# Sheet_ascii.net
KiCad netlist of a schematic drawn in Altium Designer
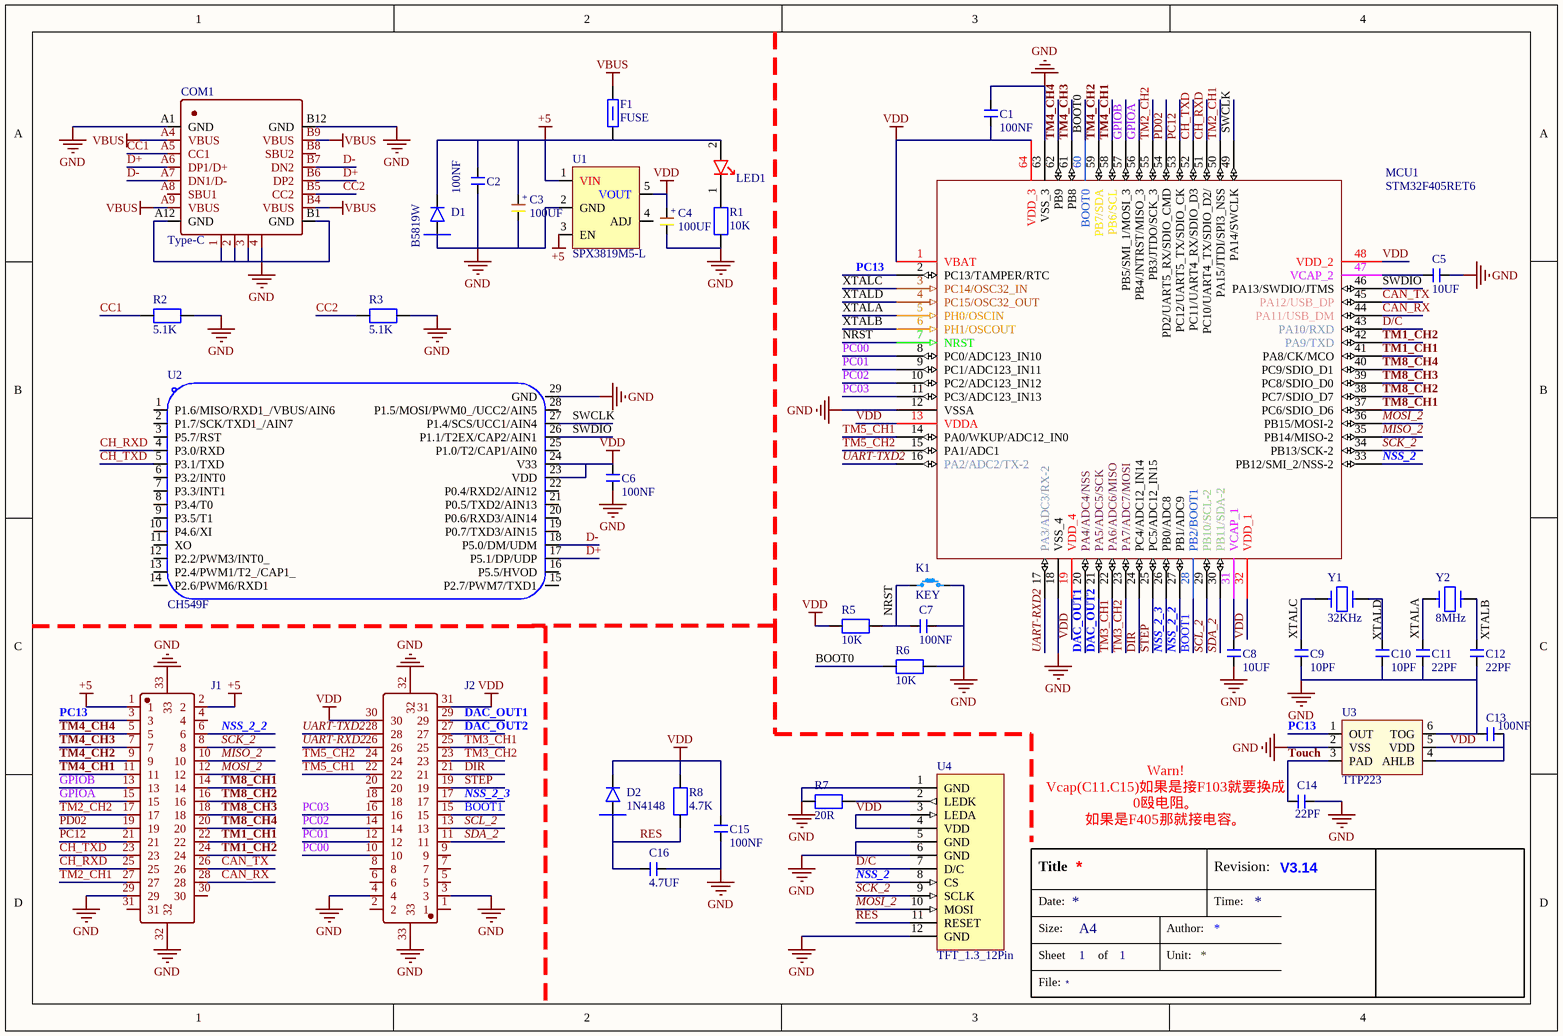
[diagram p0: Sheet_ascii.schDoc]

(export (version "E")
  (design (tool "Eeschema 10.0.6"))
  (components
    (comp (ref "C1")
      (value "100NF")
      (footprint "CAP_0603")
      (description "CAP  12~50V")
      (libsource (lib "User") (part "CAP"))
    )
    (comp (ref "C2")
      (value "100NF")
      (footprint "CAP_0603")
      (description "CAP  12~50V")
      (libsource (lib "User") (part "CAP"))
    )
    (comp (ref "C3")
      (value "100UF")
      (footprint "CAP_3216_A")
      (description "CAP  6~12V  钽电容")
      (libsource (lib "User") (part "CAP_TA"))
    )
    (comp (ref "C4")
      (value "100UF")
      (footprint "CAP_3216_A")
      (description "CAP  6~12V  钽电容")
      (libsource (lib "User") (part "CAP_TA"))
    )
    (comp (ref "C5")
      (value "10UF")
      (footprint "CAP_0603")
      (description "CAP  12~50V")
      (libsource (lib "User") (part "CAP"))
    )
    (comp (ref "C6")
      (value "100NF")
      (footprint "CAP_0603")
      (description "CAP  12~50V")
      (libsource (lib "User") (part "CAP"))
    )
    (comp (ref "C7")
      (value "100NF")
      (footprint "CAP_0603")
      (description "CAP  12~50V")
      (libsource (lib "User") (part "CAP"))
    )
    (comp (ref "C8")
      (value "10UF")
      (footprint "CAP_0603")
      (description "CAP  12~50V")
      (libsource (lib "User") (part "CAP"))
    )
    (comp (ref "C9")
      (value "10PF")
      (footprint "CAP_0603")
      (description "CAP  12~50V")
      (libsource (lib "User") (part "CAP"))
    )
    (comp (ref "C10")
      (value "10PF")
      (footprint "CAP_0603")
      (description "CAP  12~50V")
      (libsource (lib "User") (part "CAP"))
    )
    (comp (ref "C11")
      (value "22PF")
      (footprint "CAP_0603")
      (description "CAP  12~50V")
      (libsource (lib "User") (part "CAP"))
    )
    (comp (ref "C12")
      (value "22PF")
      (footprint "CAP_0603")
      (description "CAP  12~50V")
      (libsource (lib "User") (part "CAP"))
    )
    (comp (ref "C13")
      (value "100NF")
      (footprint "CAP_0603")
      (description "CAP  12~50V")
      (libsource (lib "User") (part "CAP"))
    )
    (comp (ref "C14")
      (value "22PF")
      (footprint "CAP_0603")
      (description "CAP  12~50V")
      (libsource (lib "User") (part "CAP"))
    )
    (comp (ref "C15")
      (value "100NF")
      (footprint "CAP_0603")
      (description "CAP  12~50V")
      (libsource (lib "User") (part "CAP"))
    )
    (comp (ref "C16")
      (value "4.7UF")
      (footprint "CAP_0603")
      (description "CAP  12~50V")
      (libsource (lib "User") (part "CAP"))
    )
    (comp (ref "COM1")
      (value "Type-C")
      (footprint "USB-Type-C_16A")
      (description "USB")
      (libsource (lib "User") (part "USB-type_c"))
    )
    (comp (ref "D1")
      (value "B5819W")
      (footprint "DIODE_SOD123")
      (description "Diode_肖特基/二极管")
      (libsource (lib "User") (part "Diode-SM"))
    )
    (comp (ref "D2")
      (value "1N4148")
      (footprint "DIODE_SOD123")
      (description "Diode_肖特基/二极管")
      (libsource (lib "User") (part "Diode-SM"))
    )
    (comp (ref "F1") (value "FUSE") (footprint "Fuse_0603") (libsource (lib "User") (part "FUSE")))
    (comp (ref "J1")
      (value "31PIN")
      (footprint "BTB-DM3-31P")
      (description "BTB")
      (libsource (lib "User") (part "BTB_DF3_31Pin"))
    )
    (comp (ref "J2")
      (value "31PIN")
      (footprint "BTB-DM3-31P")
      (description "BTB")
      (libsource (lib "User") (part "BTB_DF3_31Pin"))
    )
    (comp (ref "K1")
      (value "KEY")
      (footprint "KEY_SMD")
      (description "Key")
      (libsource (lib "User") (part "KEY"))
    )
    (comp (ref "LED1")
      (value "LED_R/G/B/Y")
      (footprint "LED_0603_R")
      (description "LED")
      (libsource (lib "User") (part "LED_SMT"))
    )
    (comp (ref "MCU1")
      (value "STM32F405RET6")
      (footprint "LQFP_64_10X10")
      (description "MCU")
      (libsource (lib "User") (part "STM32f4_R"))
    )
    (comp (ref "R1")
      (value "10K")
      (footprint "RESC_0603_2")
      (description "RES 贴片")
      (libsource (lib "User") (part "RES_S"))
    )
    (comp (ref "R2")
      (value "5.1K")
      (footprint "RESC_0603_2")
      (description "RES 贴片")
      (libsource (lib "User") (part "RES"))
    )
    (comp (ref "R3")
      (value "5.1K")
      (footprint "RESC_0603_2")
      (description "RES 贴片")
      (libsource (lib "User") (part "RES"))
    )
    (comp (ref "R5")
      (value "10K")
      (footprint "RESC_0603_2")
      (description "RES 贴片")
      (libsource (lib "User") (part "RES_S"))
    )
    (comp (ref "R6")
      (value "10K")
      (footprint "RESC_0603_2")
      (description "RES 贴片")
      (libsource (lib "User") (part "RES_S"))
    )
    (comp (ref "R7")
      (value "20R")
      (footprint "RESC_0603_2")
      (description "RES 贴片")
      (libsource (lib "User") (part "RES_S"))
    )
    (comp (ref "R8")
      (value "4.7K")
      (footprint "RESC_0603_2")
      (description "RES 贴片")
      (libsource (lib "User") (part "RES_S"))
    )
    (comp (ref "U1")
      (value "SPX3819M5-L")
      (footprint "SOT23_5")
      (description "DC-DC   3.3V  500ma")
      (libsource (lib "User") (part "SPX3819M5-L"))
    )
    (comp (ref "U2")
      (value "CH549F")
      (footprint "QFN28_4X4_L")
      (description "MCU")
      (fields (field (name "MANUFACTURER") "WCH(南京沁恒)"))
      (libsource (lib "User") (part "CH549F"))
    )
    (comp (ref "U3")
      (value "TTP223")
      (footprint "SOT-23-6")
      (description "触摸芯片")
      (libsource (lib "User") (part "TTP223"))
    )
    (comp (ref "U4")
      (value "TFT_1.3_12Pin")
      (footprint "LCD_1.3B")
      (description "ST7789V-SPI")
      (libsource (lib "User") (part "LCD_1.3   T"))
    )
    (comp (ref "Y1")
      (value "32KHz")
      (footprint "XTAL_SMD_3215")
      (description "CRYSTAL")
      (libsource (lib "User") (part "XTAL"))
    )
    (comp (ref "Y2")
      (value "8MHz")
      (footprint "XTAL-SMD5032-2P")
      (description "CRYSTAL")
      (libsource (lib "User") (part "XTAL"))
    )
  )
  (nets
    (net (code "1") (name "+5") (class "Default")
      (node (ref "C2") (pin "2") (pinfunction "0_2") (pintype "passive"))
      (node (ref "C3") (pin "1") (pinfunction "0_1") (pintype "passive"))
      (node (ref "D1") (pin "2") (pinfunction "N_2") (pintype "passive"))
      (node (ref "F1") (pin "1") (pinfunction "1_1") (pintype "passive"))
      (node (ref "J1") (pin "1") (pinfunction "1_1") (pintype "passive"))
      (node (ref "J1") (pin "2") (pinfunction "2_2") (pintype "passive"))
      (node (ref "LED1") (pin "2") (pinfunction "+_2") (pintype "passive"))
      (node (ref "U1") (pin "1") (pinfunction "VIN_1") (pintype "passive"))
      (node (ref "U1") (pin "3") (pinfunction "EN_3") (pintype "passive"))
    )
    (net (code "2") (name "/BOOT0") (class "Default")
      (node (ref "MCU1") (pin "60") (pinfunction "BOOT0_60") (pintype "passive"))
      (node (ref "R6") (pin "1") (pinfunction "1_1") (pintype "passive"))
    )
    (net (code "3") (name "/BOOT1") (class "Default")
      (node (ref "J2") (pin "15") (pinfunction "15_15") (pintype "passive"))
      (node (ref "MCU1") (pin "28") (pinfunction "PB2/BOOT1_28") (pintype "passive"))
    )
    (net (code "4") (name "/CAN_RX") (class "Default")
      (node (ref "J1") (pin "28") (pinfunction "28_28") (pintype "passive"))
      (node (ref "MCU1") (pin "44") (pinfunction "PA11/USB_DM_44") (pintype "bidirectional"))
    )
    (net (code "5") (name "/CAN_TX") (class "Default")
      (node (ref "J1") (pin "26") (pinfunction "26_26") (pintype "passive"))
      (node (ref "MCU1") (pin "45") (pinfunction "PA12/USB_DP_45") (pintype "bidirectional"))
    )
    (net (code "6") (name "/CC1") (class "Default")
      (node (ref "COM1") (pin "A5") (pinfunction "CC1_A5") (pintype "passive"))
      (node (ref "R2") (pin "2") (pinfunction "2_2") (pintype "passive"))
    )
    (net (code "7") (name "/CC2") (class "Default")
      (node (ref "COM1") (pin "B5") (pinfunction "CC2_B5") (pintype "passive"))
      (node (ref "R3") (pin "2") (pinfunction "2_2") (pintype "passive"))
    )
    (net (code "8") (name "/CH_RXD") (class "Default")
      (node (ref "J1") (pin "25") (pinfunction "25_25") (pintype "passive"))
      (node (ref "MCU1") (pin "51") (pinfunction "PC10/UART4_TX/SDIO_D2/_51") (pintype "bidirectional"))
      (node (ref "U2") (pin "4") (pinfunction "P3.0/RXD_4") (pintype "passive"))
    )
    (net (code "9") (name "/CH_TXD") (class "Default")
      (node (ref "J1") (pin "23") (pinfunction "23_23") (pintype "passive"))
      (node (ref "MCU1") (pin "52") (pinfunction "PC11/UART4_RX/SDIO_D3_52") (pintype "bidirectional"))
      (node (ref "U2") (pin "5") (pinfunction "P3.1/TXD_5") (pintype "passive"))
    )
    (net (code "10") (name "/D+") (class "Default")
      (node (ref "COM1") (pin "A6") (pinfunction "DP1/D+_A6") (pintype "passive"))
      (node (ref "COM1") (pin "B6") (pinfunction "DP2_B6") (pintype "passive"))
      (node (ref "U2") (pin "17") (pinfunction "P5.1/DP/UDP_17") (pintype "passive"))
    )
    (net (code "11") (name "/D-") (class "Default")
      (node (ref "COM1") (pin "A7") (pinfunction "DN1/D-_A7") (pintype "passive"))
      (node (ref "COM1") (pin "B7") (pinfunction "DN2_B7") (pintype "passive"))
      (node (ref "U2") (pin "18") (pinfunction "P5.0/DM/UDM_18") (pintype "passive"))
    )
    (net (code "12") (name "/DAC_OUT1") (class "Default")
      (node (ref "J2") (pin "29") (pinfunction "29_29") (pintype "passive"))
      (node (ref "MCU1") (pin "20") (pinfunction "PA4/ADC4/NSS_20") (pintype "bidirectional"))
    )
    (net (code "13") (name "/DAC_OUT2") (class "Default")
      (node (ref "J2") (pin "27") (pinfunction "27_27") (pintype "passive"))
      (node (ref "MCU1") (pin "21") (pinfunction "PA5/ADC5/SCK_21") (pintype "bidirectional"))
    )
    (net (code "14") (name "/DIR") (class "Default")
      (node (ref "J2") (pin "21") (pinfunction "21_21") (pintype "passive"))
      (node (ref "MCU1") (pin "24") (pinfunction "PC4/ADC12_IN14_24") (pintype "bidirectional"))
    )
    (net (code "15") (name "/D{slash}C") (class "Default")
      (node (ref "MCU1") (pin "43") (pinfunction "PA10/RXD_43") (pintype "bidirectional"))
      (node (ref "U4") (pin "7") (pinfunction "D/C_7") (pintype "passive"))
    )
    (net (code "16") (name "/GPIOA") (class "Default")
      (node (ref "J1") (pin "15") (pinfunction "15_15") (pintype "passive"))
      (node (ref "MCU1") (pin "56") (pinfunction "PB4/JNTRST/MISO_3_56") (pintype "bidirectional"))
    )
    (net (code "17") (name "/GPIOB") (class "Default")
      (node (ref "J1") (pin "13") (pinfunction "13_13") (pintype "passive"))
      (node (ref "MCU1") (pin "57") (pinfunction "PB5/SMI_1/MOSI_3_57") (pintype "bidirectional"))
    )
    (net (code "18") (name "/MISO_2") (class "Default")
      (node (ref "J1") (pin "10") (pinfunction "10_10") (pintype "passive"))
      (node (ref "MCU1") (pin "35") (pinfunction "PB14/MISO-2_35") (pintype "bidirectional"))
    )
    (net (code "19") (name "/MOSI_2") (class "Default")
      (node (ref "J1") (pin "12") (pinfunction "12_12") (pintype "passive"))
      (node (ref "MCU1") (pin "36") (pinfunction "PB15/MOSI-2_36") (pintype "bidirectional"))
      (node (ref "U4") (pin "10") (pinfunction "MOSI_10") (pintype "input"))
    )
    (net (code "20") (name "/NRST") (class "Default")
      (node (ref "C7") (pin "2") (pinfunction "0_2") (pintype "passive"))
      (node (ref "K1") (pin "2") (pintype "passive"))
      (node (ref "MCU1") (pin "7") (pinfunction "NRST_7") (pintype "input"))
      (node (ref "R5") (pin "2") (pinfunction "2_2") (pintype "passive"))
    )
    (net (code "21") (name "/NSS_2") (class "Default")
      (node (ref "MCU1") (pin "33") (pinfunction "PB12/SMI_2/NSS-2_33") (pintype "bidirectional"))
      (node (ref "U4") (pin "8") (pinfunction "CS_8") (pintype "input"))
    )
    (net (code "22") (name "/NSS_2_2") (class "Default")
      (node (ref "J1") (pin "6") (pinfunction "6_6") (pintype "passive"))
      (node (ref "MCU1") (pin "27") (pinfunction "PB1/ADC9_27") (pintype "bidirectional"))
    )
    (net (code "23") (name "/NSS_2_3") (class "Default")
      (node (ref "J2") (pin "17") (pinfunction "17_17") (pintype "passive"))
      (node (ref "MCU1") (pin "26") (pinfunction "PB0/ADC8_26") (pintype "bidirectional"))
    )
    (net (code "24") (name "/PC00") (class "Default")
      (node (ref "J2") (pin "10") (pinfunction "10_10") (pintype "passive"))
      (node (ref "MCU1") (pin "8") (pinfunction "PC0/ADC123_IN10_8") (pintype "bidirectional"))
    )
    (net (code "25") (name "/PC01") (class "Default")
      (node (ref "J2") (pin "12") (pinfunction "12_12") (pintype "passive"))
      (node (ref "MCU1") (pin "9") (pinfunction "PC1/ADC123_IN11_9") (pintype "bidirectional"))
    )
    (net (code "26") (name "/PC02") (class "Default")
      (node (ref "J2") (pin "14") (pinfunction "14_14") (pintype "passive"))
      (node (ref "MCU1") (pin "10") (pinfunction "PC2/ADC123_IN12_10") (pintype "bidirectional"))
    )
    (net (code "27") (name "/PC03") (class "Default")
      (node (ref "J2") (pin "16") (pinfunction "16_16") (pintype "passive"))
      (node (ref "MCU1") (pin "11") (pinfunction "PC3/ADC123_IN13_11") (pintype "bidirectional"))
    )
    (net (code "28") (name "/PC12") (class "Default")
      (node (ref "J1") (pin "21") (pinfunction "21_21") (pintype "passive"))
      (node (ref "MCU1") (pin "53") (pinfunction "PC12/UART5_TX/SDIO_CK_53") (pintype "bidirectional"))
    )
    (net (code "29") (name "/PC13") (class "Default")
      (node (ref "J1") (pin "3") (pinfunction "3_3") (pintype "passive"))
      (node (ref "MCU1") (pin "2") (pinfunction "PC13/TAMPER/RTC_2") (pintype "bidirectional"))
      (node (ref "U3") (pin "1") (pinfunction "OUT_1") (pintype "passive"))
    )
    (net (code "30") (name "/PD02") (class "Default")
      (node (ref "J1") (pin "19") (pinfunction "19_19") (pintype "passive"))
      (node (ref "MCU1") (pin "54") (pinfunction "PD2/UART5_RX/SDIO_CMD_54") (pintype "bidirectional"))
    )
    (net (code "31") (name "/RES") (class "Default")
      (node (ref "C16") (pin "1") (pinfunction "0_1") (pintype "passive"))
      (node (ref "D2") (pin "1") (pinfunction "P_1") (pintype "passive"))
      (node (ref "R8") (pin "2") (pinfunction "2_2") (pintype "passive"))
      (node (ref "U4") (pin "11") (pinfunction "RESET_11") (pintype "passive"))
    )
    (net (code "32") (name "/SCK_2") (class "Default")
      (node (ref "J1") (pin "8") (pinfunction "8_8") (pintype "passive"))
      (node (ref "MCU1") (pin "34") (pinfunction "PB13/SCK-2_34") (pintype "bidirectional"))
      (node (ref "U4") (pin "9") (pinfunction "SCLK_9") (pintype "input"))
    )
    (net (code "33") (name "/SCL_2") (class "Default")
      (node (ref "J2") (pin "13") (pinfunction "13_13") (pintype "passive"))
      (node (ref "MCU1") (pin "29") (pinfunction "PB10/SCL-2_29") (pintype "bidirectional"))
    )
    (net (code "34") (name "/SDA_2") (class "Default")
      (node (ref "J2") (pin "11") (pinfunction "11_11") (pintype "passive"))
      (node (ref "MCU1") (pin "30") (pinfunction "PB11/SDA-2_30") (pintype "bidirectional"))
    )
    (net (code "35") (name "/STEP") (class "Default")
      (node (ref "J2") (pin "19") (pinfunction "19_19") (pintype "passive"))
      (node (ref "MCU1") (pin "25") (pinfunction "PC5/ADC12_IN15_25") (pintype "bidirectional"))
    )
    (net (code "36") (name "/SWCLK") (class "Default")
      (node (ref "MCU1") (pin "49") (pinfunction "PA14/SWCLK_49") (pintype "bidirectional"))
      (node (ref "U2") (pin "27") (pinfunction "P1.4/SCS/UCC1/AIN4_27") (pintype "passive"))
    )
    (net (code "37") (name "/SWDIO") (class "Default")
      (node (ref "MCU1") (pin "46") (pinfunction "PA13/SWDIO/JTMS_46") (pintype "bidirectional"))
      (node (ref "U2") (pin "26") (pinfunction "P1.1/T2EX/CAP2/AIN1_26") (pintype "passive"))
    )
    (net (code "38") (name "/TM1_CH1") (class "Default")
      (node (ref "J1") (pin "22") (pinfunction "22_22") (pintype "passive"))
      (node (ref "MCU1") (pin "41") (pinfunction "PA8/CK/MCO_41") (pintype "bidirectional"))
    )
    (net (code "39") (name "/TM1_CH2") (class "Default")
      (node (ref "J1") (pin "24") (pinfunction "24_24") (pintype "passive"))
      (node (ref "MCU1") (pin "42") (pinfunction "PA9/TXD_42") (pintype "bidirectional"))
    )
    (net (code "40") (name "/TM2_CH1") (class "Default")
      (node (ref "J1") (pin "27") (pinfunction "27_27") (pintype "passive"))
      (node (ref "MCU1") (pin "50") (pinfunction "PA15/JTDI/SPI3_NSS_50") (pintype "bidirectional"))
    )
    (net (code "41") (name "/TM2_CH2") (class "Default")
      (node (ref "J1") (pin "17") (pinfunction "17_17") (pintype "passive"))
      (node (ref "MCU1") (pin "55") (pinfunction "PB3/JTDO/SCK_3_55") (pintype "bidirectional"))
    )
    (net (code "42") (name "/TM3_CH1") (class "Default")
      (node (ref "J2") (pin "25") (pinfunction "25_25") (pintype "passive"))
      (node (ref "MCU1") (pin "22") (pinfunction "PA6/ADC6/MISO_22") (pintype "bidirectional"))
    )
    (net (code "43") (name "/TM3_CH2") (class "Default")
      (node (ref "J2") (pin "23") (pinfunction "23_23") (pintype "passive"))
      (node (ref "MCU1") (pin "23") (pinfunction "PA7/ADC7/MOSI_23") (pintype "bidirectional"))
    )
    (net (code "44") (name "/TM4_CH1") (class "Default")
      (node (ref "J1") (pin "11") (pinfunction "11_11") (pintype "passive"))
      (node (ref "MCU1") (pin "58") (pinfunction "PB6/SCL_58") (pintype "bidirectional"))
    )
    (net (code "45") (name "/TM4_CH2") (class "Default")
      (node (ref "J1") (pin "9") (pinfunction "9_9") (pintype "passive"))
      (node (ref "MCU1") (pin "59") (pinfunction "PB7/SDA_59") (pintype "bidirectional"))
    )
    (net (code "46") (name "/TM4_CH3") (class "Default")
      (node (ref "J1") (pin "7") (pinfunction "7_7") (pintype "passive"))
      (node (ref "MCU1") (pin "61") (pinfunction "PB8_61") (pintype "bidirectional"))
    )
    (net (code "47") (name "/TM4_CH4") (class "Default")
      (node (ref "J1") (pin "5") (pinfunction "5_5") (pintype "passive"))
      (node (ref "MCU1") (pin "62") (pinfunction "PB9_62") (pintype "bidirectional"))
    )
    (net (code "48") (name "/TM5_CH1") (class "Default")
      (node (ref "J2") (pin "22") (pinfunction "22_22") (pintype "passive"))
      (node (ref "MCU1") (pin "14") (pinfunction "PA0/WKUP/ADC12_IN0_14") (pintype "bidirectional"))
    )
    (net (code "49") (name "/TM5_CH2") (class "Default")
      (node (ref "J2") (pin "24") (pinfunction "24_24") (pintype "passive"))
      (node (ref "MCU1") (pin "15") (pinfunction "PA1/ADC1_15") (pintype "bidirectional"))
    )
    (net (code "50") (name "/TM8_CH1") (class "Default")
      (node (ref "J1") (pin "14") (pinfunction "14_14") (pintype "passive"))
      (node (ref "MCU1") (pin "37") (pinfunction "PC6/SDIO_D6_37") (pintype "bidirectional"))
    )
    (net (code "51") (name "/TM8_CH2") (class "Default")
      (node (ref "J1") (pin "16") (pinfunction "16_16") (pintype "passive"))
      (node (ref "MCU1") (pin "38") (pinfunction "PC7/SDIO_D7_38") (pintype "bidirectional"))
    )
    (net (code "52") (name "/TM8_CH3") (class "Default")
      (node (ref "J1") (pin "18") (pinfunction "18_18") (pintype "passive"))
      (node (ref "MCU1") (pin "39") (pinfunction "PC8/SDIO_D0_39") (pintype "bidirectional"))
    )
    (net (code "53") (name "/TM8_CH4") (class "Default")
      (node (ref "J1") (pin "20") (pinfunction "20_20") (pintype "passive"))
      (node (ref "MCU1") (pin "40") (pinfunction "PC9/SDIO_D1_40") (pintype "bidirectional"))
    )
    (net (code "54") (name "/Touch") (class "Default")
      (node (ref "C14") (pin "1") (pinfunction "0_1") (pintype "passive"))
      (node (ref "U3") (pin "3") (pinfunction "PAD_3") (pintype "passive"))
    )
    (net (code "55") (name "/UART-RXD2") (class "Default")
      (node (ref "J2") (pin "26") (pinfunction "26_26") (pintype "passive"))
      (node (ref "MCU1") (pin "17") (pinfunction "PA3/ADC3/RX-2_17") (pintype "bidirectional"))
    )
    (net (code "56") (name "/UART-TXD2") (class "Default")
      (node (ref "J2") (pin "28") (pinfunction "28_28") (pintype "passive"))
      (node (ref "MCU1") (pin "16") (pinfunction "PA2/ADC2/TX-2_16") (pintype "bidirectional"))
    )
    (net (code "57") (name "/XTALA") (class "Default")
      (node (ref "C11") (pin "1") (pinfunction "0_1") (pintype "passive"))
      (node (ref "MCU1") (pin "5") (pinfunction "PH0/OSCIN_5") (pintype "input"))
      (node (ref "Y2") (pin "2") (pinfunction "2_2") (pintype "passive"))
    )
    (net (code "58") (name "/XTALB") (class "Default")
      (node (ref "C12") (pin "1") (pinfunction "0_1") (pintype "passive"))
      (node (ref "MCU1") (pin "6") (pinfunction "PH1/OSCOUT_6") (pintype "input"))
      (node (ref "Y2") (pin "1") (pinfunction "1_1") (pintype "passive"))
    )
    (net (code "59") (name "/XTALC") (class "Default")
      (node (ref "C9") (pin "1") (pinfunction "0_1") (pintype "passive"))
      (node (ref "MCU1") (pin "3") (pinfunction "PC14/OSC32_IN_3") (pintype "input"))
      (node (ref "Y1") (pin "2") (pinfunction "2_2") (pintype "passive"))
    )
    (net (code "60") (name "/XTALD") (class "Default")
      (node (ref "C10") (pin "1") (pinfunction "0_1") (pintype "passive"))
      (node (ref "MCU1") (pin "4") (pinfunction "PC15/OSC32_OUT_4") (pintype "input"))
      (node (ref "Y1") (pin "1") (pinfunction "1_1") (pintype "passive"))
    )
    (net (code "61") (name "GND") (class "Default")
      (node (ref "C1") (pin "1") (pinfunction "0_1") (pintype "passive"))
      (node (ref "C10") (pin "2") (pinfunction "0_2") (pintype "passive"))
      (node (ref "C11") (pin "2") (pinfunction "0_2") (pintype "passive"))
      (node (ref "C12") (pin "2") (pinfunction "0_2") (pintype "passive"))
      (node (ref "C13") (pin "1") (pinfunction "0_1") (pintype "passive"))
      (node (ref "C14") (pin "2") (pinfunction "0_2") (pintype "passive"))
      (node (ref "C15") (pin "2") (pinfunction "0_2") (pintype "passive"))
      (node (ref "C16") (pin "2") (pinfunction "0_2") (pintype "passive"))
      (node (ref "C2") (pin "1") (pinfunction "0_1") (pintype "passive"))
      (node (ref "C3") (pin "2") (pinfunction "0_2") (pintype "passive"))
      (node (ref "C4") (pin "2") (pinfunction "0_2") (pintype "passive"))
      (node (ref "C5") (pin "1") (pinfunction "0_1") (pintype "passive"))
      (node (ref "C6") (pin "1") (pinfunction "0_1") (pintype "passive"))
      (node (ref "C7") (pin "1") (pinfunction "0_1") (pintype "passive"))
      (node (ref "C8") (pin "1") (pinfunction "0_1") (pintype "passive"))
      (node (ref "C9") (pin "2") (pinfunction "0_2") (pintype "passive"))
      (node (ref "COM1") (pin "1") (pinfunction "1_1") (pintype "passive"))
      (node (ref "COM1") (pin "2") (pinfunction "2_2") (pintype "passive"))
      (node (ref "COM1") (pin "3") (pinfunction "3_3") (pintype "passive"))
      (node (ref "COM1") (pin "4") (pinfunction "4_4") (pintype "passive"))
      (node (ref "COM1") (pin "A1") (pinfunction "GND_A1") (pintype "passive"))
      (node (ref "COM1") (pin "A12") (pinfunction "GND_A12") (pintype "passive"))
      (node (ref "COM1") (pin "B1") (pinfunction "GND_B1") (pintype "passive"))
      (node (ref "COM1") (pin "B12") (pinfunction "GND_B12") (pintype "passive"))
      (node (ref "D1") (pin "1") (pinfunction "P_1") (pintype "passive"))
      (node (ref "J1") (pin "29") (pinfunction "29_29") (pintype "passive"))
      (node (ref "J1") (pin "32") (pinfunction "32_32") (pintype "passive"))
      (node (ref "J1") (pin "33") (pinfunction "33_33") (pintype "passive"))
      (node (ref "J2") (pin "3") (pinfunction "3_3") (pintype "passive"))
      (node (ref "J2") (pin "32") (pinfunction "32_32") (pintype "passive"))
      (node (ref "J2") (pin "33") (pinfunction "33_33") (pintype "passive"))
      (node (ref "J2") (pin "4") (pinfunction "4_4") (pintype "passive"))
      (node (ref "K1") (pin "1") (pintype "passive"))
      (node (ref "MCU1") (pin "12") (pinfunction "VSSA_12") (pintype "power_in"))
      (node (ref "MCU1") (pin "18") (pinfunction "VSS_4_18") (pintype "power_in"))
      (node (ref "MCU1") (pin "63") (pinfunction "VSS_3_63") (pintype "power_in"))
      (node (ref "R1") (pin "1") (pinfunction "1_1") (pintype "passive"))
      (node (ref "R2") (pin "1") (pinfunction "1_1") (pintype "passive"))
      (node (ref "R3") (pin "1") (pinfunction "1_1") (pintype "passive"))
      (node (ref "R6") (pin "2") (pinfunction "2_2") (pintype "passive"))
      (node (ref "R7") (pin "1") (pinfunction "1_1") (pintype "passive"))
      (node (ref "U1") (pin "2") (pinfunction "GND_2") (pintype "passive"))
      (node (ref "U2") (pin "29") (pinfunction "GND_29") (pintype "passive"))
      (node (ref "U3") (pin "2") (pinfunction "VSS_2") (pintype "passive"))
      (node (ref "U3") (pin "6") (pinfunction "TOG_6") (pintype "passive"))
      (node (ref "U4") (pin "1") (pinfunction "GND_1") (pintype "passive"))
      (node (ref "U4") (pin "12") (pinfunction "GND_12") (pintype "passive"))
      (node (ref "U4") (pin "5") (pinfunction "GND_5") (pintype "passive"))
      (node (ref "U4") (pin "6") (pinfunction "GND_6") (pintype "passive"))
    )
    (net (code "62") (name "Net-(LED1--)") (class "Default")
      (node (ref "LED1") (pin "1") (pinfunction "-_1") (pintype "passive"))
      (node (ref "R1") (pin "2") (pinfunction "2_2") (pintype "passive"))
    )
    (net (code "63") (name "Net-(MCU1-VCAP_1)") (class "Default")
      (node (ref "C8") (pin "2") (pinfunction "0_2") (pintype "passive"))
      (node (ref "MCU1") (pin "31") (pinfunction "VCAP_1_31") (pintype "passive"))
    )
    (net (code "64") (name "Net-(MCU1-VCAP_2)") (class "Default")
      (node (ref "C5") (pin "2") (pinfunction "0_2") (pintype "passive"))
      (node (ref "MCU1") (pin "47") (pinfunction "VCAP_2_47") (pintype "passive"))
    )
    (net (code "65") (name "Net-(U4-LEDK)") (class "Default")
      (node (ref "R7") (pin "2") (pinfunction "2_2") (pintype "passive"))
      (node (ref "U4") (pin "2") (pinfunction "LEDK_2") (pintype "output"))
    )
    (net (code "66") (name "VBUS") (class "Default")
      (node (ref "COM1") (pin "A4") (pinfunction "VBUS_A4") (pintype "passive"))
      (node (ref "COM1") (pin "A9") (pinfunction "VBUS_A9") (pintype "passive"))
      (node (ref "COM1") (pin "B4") (pinfunction "VBUS_B4") (pintype "passive"))
      (node (ref "COM1") (pin "B9") (pinfunction "VBUS_B9") (pintype "passive"))
      (node (ref "F1") (pin "2") (pinfunction "2_2") (pintype "passive"))
    )
    (net (code "67") (name "VDD") (class "Default")
      (node (ref "C1") (pin "2") (pinfunction "0_2") (pintype "passive"))
      (node (ref "C13") (pin "2") (pinfunction "0_2") (pintype "passive"))
      (node (ref "C15") (pin "1") (pinfunction "0_1") (pintype "passive"))
      (node (ref "C4") (pin "1") (pinfunction "0_1") (pintype "passive"))
      (node (ref "C6") (pin "2") (pinfunction "0_2") (pintype "passive"))
      (node (ref "D2") (pin "2") (pinfunction "N_2") (pintype "passive"))
      (node (ref "J2") (pin "30") (pinfunction "30_30") (pintype "passive"))
      (node (ref "J2") (pin "31") (pinfunction "31_31") (pintype "passive"))
      (node (ref "MCU1") (pin "1") (pinfunction "VBAT_1") (pintype "power_in"))
      (node (ref "MCU1") (pin "13") (pinfunction "VDDA_13") (pintype "power_in"))
      (node (ref "MCU1") (pin "19") (pinfunction "VDD_4_19") (pintype "power_in"))
      (node (ref "MCU1") (pin "32") (pinfunction "VDD_1_32") (pintype "power_in"))
      (node (ref "MCU1") (pin "48") (pinfunction "VDD_2_48") (pintype "power_in"))
      (node (ref "MCU1") (pin "64") (pinfunction "VDD_3_64") (pintype "power_in"))
      (node (ref "R5") (pin "1") (pinfunction "1_1") (pintype "passive"))
      (node (ref "R8") (pin "1") (pinfunction "1_1") (pintype "passive"))
      (node (ref "U1") (pin "5") (pinfunction "VOUT_5") (pintype "passive"))
      (node (ref "U2") (pin "23") (pinfunction "VDD_23") (pintype "passive"))
      (node (ref "U2") (pin "24") (pinfunction "V33_24") (pintype "passive"))
      (node (ref "U3") (pin "4") (pinfunction "AHLB_4") (pintype "passive"))
      (node (ref "U3") (pin "5") (pinfunction "VDD_5") (pintype "passive"))
      (node (ref "U4") (pin "3") (pinfunction "LEDA_3") (pintype "input"))
      (node (ref "U4") (pin "4") (pinfunction "VDD_4") (pintype "passive"))
    )
    (net (code "68") (name "unconnected-(COM1-SBU1-PadA8)") (class "Default")
      (node (ref "COM1") (pin "A8") (pinfunction "SBU1_A8") (pintype "passive"))
    )
    (net (code "69") (name "unconnected-(COM1-SBU2-PadB8)") (class "Default")
      (node (ref "COM1") (pin "B8") (pinfunction "SBU2_B8") (pintype "passive"))
    )
    (net (code "70") (name "unconnected-(J1-Pad4)") (class "Default")
      (node (ref "J1") (pin "4") (pinfunction "4_4") (pintype "passive"))
    )
    (net (code "71") (name "unconnected-(J1-Pad30)") (class "Default")
      (node (ref "J1") (pin "30") (pinfunction "30_30") (pintype "passive"))
    )
    (net (code "72") (name "unconnected-(J1-Pad31)") (class "Default")
      (node (ref "J1") (pin "31") (pinfunction "31_31") (pintype "passive"))
    )
    (net (code "73") (name "unconnected-(J2-Pad1)") (class "Default")
      (node (ref "J2") (pin "1") (pinfunction "1_1") (pintype "passive"))
    )
    (net (code "74") (name "unconnected-(J2-Pad2)") (class "Default")
      (node (ref "J2") (pin "2") (pinfunction "2_2") (pintype "passive"))
    )
    (net (code "75") (name "unconnected-(J2-Pad5)") (class "Default")
      (node (ref "J2") (pin "5") (pinfunction "5_5") (pintype "passive"))
    )
    (net (code "76") (name "unconnected-(J2-Pad6)") (class "Default")
      (node (ref "J2") (pin "6") (pinfunction "6_6") (pintype "passive"))
    )
    (net (code "77") (name "unconnected-(J2-Pad7)") (class "Default")
      (node (ref "J2") (pin "7") (pinfunction "7_7") (pintype "passive"))
    )
    (net (code "78") (name "unconnected-(J2-Pad8)") (class "Default")
      (node (ref "J2") (pin "8") (pinfunction "8_8") (pintype "passive"))
    )
    (net (code "79") (name "unconnected-(J2-Pad9)") (class "Default")
      (node (ref "J2") (pin "9") (pinfunction "9_9") (pintype "passive"))
    )
    (net (code "80") (name "unconnected-(J2-Pad18)") (class "Default")
      (node (ref "J2") (pin "18") (pinfunction "18_18") (pintype "passive"))
    )
    (net (code "81") (name "unconnected-(J2-Pad20)") (class "Default")
      (node (ref "J2") (pin "20") (pinfunction "20_20") (pintype "passive"))
    )
    (net (code "82") (name "unconnected-(U1-ADJ-Pad4)") (class "Default")
      (node (ref "U1") (pin "4") (pinfunction "ADJ_4") (pintype "passive"))
    )
    (net (code "83") (name "unconnected-(U2-P0.4{slash}RXD2{slash}AIN12-Pad22)") (class "Default")
      (node (ref "U2") (pin "22") (pinfunction "P0.4/RXD2/AIN12_22") (pintype "passive"))
    )
    (net (code "84") (name "unconnected-(U2-P0.5{slash}TXD2{slash}AIN13-Pad21)") (class "Default")
      (node (ref "U2") (pin "21") (pinfunction "P0.5/TXD2/AIN13_21") (pintype "passive"))
    )
    (net (code "85") (name "unconnected-(U2-P0.6{slash}RXD3{slash}AIN14-Pad20)") (class "Default")
      (node (ref "U2") (pin "20") (pinfunction "P0.6/RXD3/AIN14_20") (pintype "passive"))
    )
    (net (code "86") (name "unconnected-(U2-P0.7{slash}TXD3{slash}AIN15-Pad19)") (class "Default")
      (node (ref "U2") (pin "19") (pinfunction "P0.7/TXD3/AIN15_19") (pintype "passive"))
    )
    (net (code "87") (name "unconnected-(U2-P1.0{slash}T2{slash}CAP1{slash}AIN0-Pad25)") (class "Default")
      (node (ref "U2") (pin "25") (pinfunction "P1.0/T2/CAP1/AIN0_25") (pintype "passive"))
    )
    (net (code "88") (name "unconnected-(U2-P1.5{slash}MOSI{slash}PWM0_{slash}UCC2{slash}AIN5-Pad28)") (class "Default")
      (node (ref "U2") (pin "28") (pinfunction "P1.5/MOSI/PWM0_/UCC2/AIN5_28") (pintype "passive"))
    )
    (net (code "89") (name "unconnected-(U2-P1.6{slash}MISO{slash}RXD1_{slash}VBUS{slash}AIN6-Pad1)") (class "Default")
      (node (ref "U2") (pin "1") (pinfunction "P1.6/MISO/RXD1_/VBUS/AIN6_1") (pintype "passive"))
    )
    (net (code "90") (name "unconnected-(U2-P1.7{slash}SCK{slash}TXD1_{slash}AIN7-Pad2)") (class "Default")
      (node (ref "U2") (pin "2") (pinfunction "P1.7/SCK/TXD1_/AIN7_2") (pintype "passive"))
    )
    (net (code "91") (name "unconnected-(U2-P2.2{slash}PWM3{slash}INT0_-Pad12)") (class "Default")
      (node (ref "U2") (pin "12") (pinfunction "P2.2/PWM3/INT0__12") (pintype "passive"))
    )
    (net (code "92") (name "unconnected-(U2-P2.4{slash}PWM1{slash}T2_{slash}CAP1_-Pad13)") (class "Default")
      (node (ref "U2") (pin "13") (pinfunction "P2.4/PWM1/T2_/CAP1__13") (pintype "passive"))
    )
    (net (code "93") (name "unconnected-(U2-P2.6{slash}PWM6{slash}RXD1-Pad14)") (class "Default")
      (node (ref "U2") (pin "14") (pinfunction "P2.6/PWM6/RXD1_14") (pintype "passive"))
    )
    (net (code "94") (name "unconnected-(U2-P2.7{slash}PWM7{slash}TXD1-Pad15)") (class "Default")
      (node (ref "U2") (pin "15") (pinfunction "P2.7/PWM7/TXD1_15") (pintype "passive"))
    )
    (net (code "95") (name "unconnected-(U2-P3.2{slash}INT0-Pad6)") (class "Default")
      (node (ref "U2") (pin "6") (pinfunction "P3.2/INT0_6") (pintype "passive"))
    )
    (net (code "96") (name "unconnected-(U2-P3.3{slash}INT1-Pad7)") (class "Default")
      (node (ref "U2") (pin "7") (pinfunction "P3.3/INT1_7") (pintype "passive"))
    )
    (net (code "97") (name "unconnected-(U2-P3.4{slash}T0-Pad8)") (class "Default")
      (node (ref "U2") (pin "8") (pinfunction "P3.4/T0_8") (pintype "passive"))
    )
    (net (code "98") (name "unconnected-(U2-P3.5{slash}T1-Pad9)") (class "Default")
      (node (ref "U2") (pin "9") (pinfunction "P3.5/T1_9") (pintype "passive"))
    )
    (net (code "99") (name "unconnected-(U2-P4.6{slash}XI-Pad10)") (class "Default")
      (node (ref "U2") (pin "10") (pinfunction "P4.6/XI_10") (pintype "passive"))
    )
    (net (code "100") (name "unconnected-(U2-P5.5{slash}HVOD-Pad16)") (class "Default")
      (node (ref "U2") (pin "16") (pinfunction "P5.5/HVOD_16") (pintype "passive"))
    )
    (net (code "101") (name "unconnected-(U2-P5.7{slash}RST-Pad3)") (class "Default")
      (node (ref "U2") (pin "3") (pinfunction "P5.7/RST_3") (pintype "passive"))
    )
    (net (code "102") (name "unconnected-(U2-XO-Pad11)") (class "Default")
      (node (ref "U2") (pin "11") (pinfunction "XO_11") (pintype "passive"))
    )
  )
)
